# Car_Circuitry.net
KiCad netlist of a schematic drawn in Altium Designer
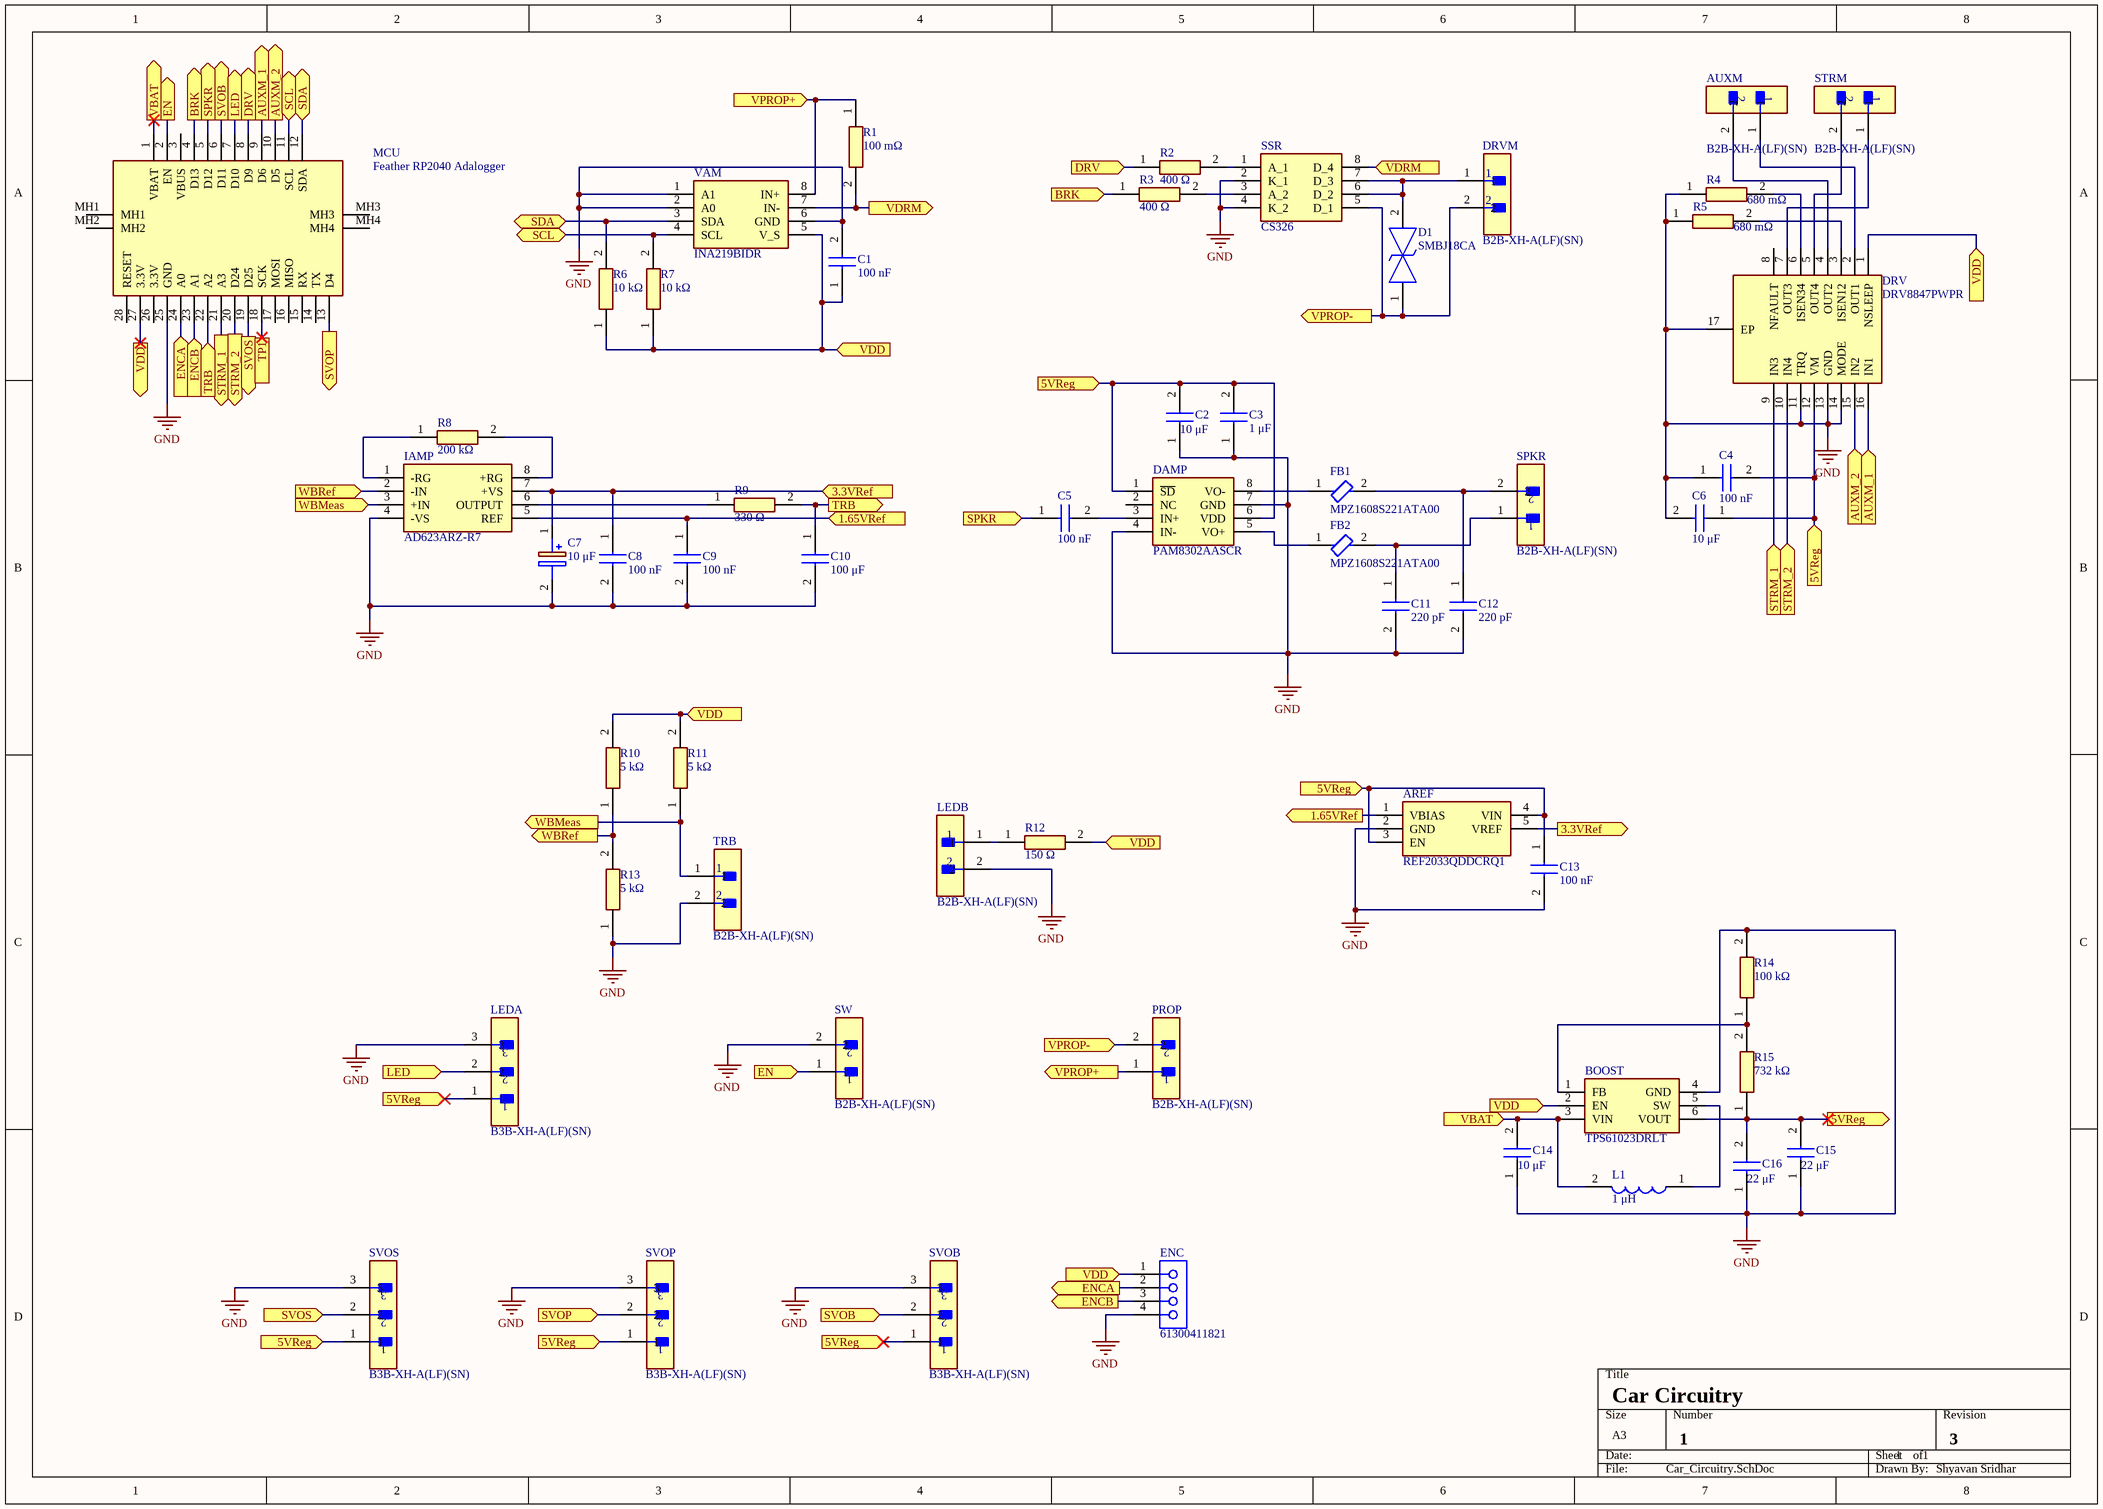
[diagram p0: Car_Circuitry.SchDoc]

(export (version "E")
  (design (tool "Eeschema 10.0.6"))
  (components
    (comp (ref "AREF")
      (value "REF2033QDDCRQ1")
      (footprint "SamacSys:SOT95P280X110-5N")
      (description "Integrated Circuit")
      (fields (field (name "MOUSER PART NUMBER") "595-REF2033QDDCRQ1"))
      (libsource (lib "*") (part "REF2033QDDCRQ1"))
    )
    (comp (ref "AUXM")
      (value "B2B-XH-A(LF)(SN)")
      (footprint "FP-B2B-XH-A_LF_SN-MFG")
      (description "CONN HEADER VERT 2POS 2.5MM")
      (libsource (lib "Altium Content Vault") (part "3bc925449376181038e59eaffc5286c"))
    )
    (comp (ref "BOOST")
      (value "TPS61023DRLT")
      (footprint "SamacSys:SOTFL50P160X60-6N")
      (description "Integrated Circuit")
      (fields (field (name "MOUSER PART NUMBER") "595-TPS61023DRLT"))
      (libsource (lib "*") (part "TPS61023DRLT"))
    )
    (comp (ref "C1")
      (value "100 nF")
      (footprint "SamacSys:CAPC2012X95N")
      (description "Capacitor")
      (fields
        (field (name "MANUFACTURER_PART_NUMBER") "CL21B104KBCNNNC")
        (field (name "MOUSER PART NUMBER") "187-CL21B104KBCNNNC")
      )
      (libsource (lib "SamacSys") (part "CL21B104KBCNNNC"))
    )
    (comp (ref "C2")
      (value "10 μF")
      (footprint "CAPC2012X140N")
      (description "Capacitor")
      (fields
        (field (name "MANUFACTURER_PART_NUMBER") "CL21B106KOQNNNE")
        (field (name "MOUSER PART NUMBER") "187-CL21B106KOQNNNE")
      )
      (libsource (lib "SamacSys") (part "CL21B106KOQNNNE"))
    )
    (comp (ref "C3")
      (value "1 μF")
      (footprint "SamacSys:C0402C104J4RACTU")
      (description "Capacitor")
      (fields
        (field (name "MANUFACTURER_PART_NUMBER") "C0402C105K9PACTU")
        (field (name "MOUSER PART NUMBER") "80-C0402C105K9P")
      )
      (libsource (lib "SamacSys") (part "C0402C105K9PACTU"))
    )
    (comp (ref "C4")
      (value "100 nF")
      (footprint "SamacSys:CAPC2012X95N")
      (description "Capacitor")
      (fields
        (field (name "MANUFACTURER_PART_NUMBER") "CL21B104KBCNNNC")
        (field (name "MOUSER PART NUMBER") "187-CL21B104KBCNNNC")
      )
      (libsource (lib "SamacSys") (part "CL21B104KBCNNNC"))
    )
    (comp (ref "C5")
      (value "100 nF")
      (footprint "SamacSys:CAPC2012X95N")
      (description "Capacitor")
      (fields
        (field (name "MANUFACTURER_PART_NUMBER") "CL21B104KBCNNNC")
        (field (name "MOUSER PART NUMBER") "187-CL21B104KBCNNNC")
      )
      (libsource (lib "SamacSys") (part "CL21B104KBCNNNC"))
    )
    (comp (ref "C6")
      (value "10 μF")
      (footprint "SamacSys:CAPC2012X140N")
      (description "Capacitor")
      (fields
        (field (name "MANUFACTURER_PART_NUMBER") "CL21B106KOQNNNE")
        (field (name "MOUSER PART NUMBER") "187-CL21B106KOQNNNE")
      )
      (libsource (lib "*") (part "CL21B106KOQNNNE"))
    )
    (comp (ref "C7")
      (value "10 μF")
      (footprint "SamacSys:CAPPM3528X210N")
      (description "Capacitor Polarised")
      (fields
        (field (name "MANUFACTURER_PART_NUMBER") "293D106X9016B2TE3")
        (field (name "MOUSER PART NUMBER") "74-293D106X9016B2TE3")
      )
      (libsource (lib "*") (part "293D106X9016B2TE3"))
    )
    (comp (ref "C8")
      (value "100 nF")
      (footprint "SamacSys:CAPC2012X95N")
      (description "Capacitor")
      (fields
        (field (name "MANUFACTURER_PART_NUMBER") "CL21B104KBCNNNC")
        (field (name "MOUSER PART NUMBER") "187-CL21B104KBCNNNC")
      )
      (libsource (lib "SamacSys") (part "CL21B104KBCNNNC"))
    )
    (comp (ref "C9")
      (value "100 nF")
      (footprint "SamacSys:CAPC2012X95N")
      (description "Capacitor")
      (fields
        (field (name "MANUFACTURER_PART_NUMBER") "CL21B104KBCNNNC")
        (field (name "MOUSER PART NUMBER") "187-CL21B104KBCNNNC")
      )
      (libsource (lib "SamacSys") (part "CL21B104KBCNNNC"))
    )
    (comp (ref "C10")
      (value "100 μF")
      (footprint "SamacSys:GRM31x")
      (description "Capacitor")
      (fields
        (field (name "MANUFACTURER_PART_NUMBER") "GRM31CD80J107MEA8K")
        (field (name "MOUSER PART NUMBER") "81-GRM31CD80J107MA8K")
      )
      (libsource (lib "*") (part "GRM31CD80J107MEA8K"))
    )
    (comp (ref "C11")
      (value "220 pF")
      (footprint "SamacSys:GRM033D70J224ME01D")
      (description "Capacitor")
      (fields
        (field (name "MANUFACTURER_PART_NUMBER") "GRM033R71C221KA01D")
        (field (name "MOUSER PART NUMBER") "81-GRM033R71C221KA1D")
      )
      (libsource (lib "*") (part "GRM033R71C221KA01D"))
    )
    (comp (ref "C12")
      (value "220 pF")
      (footprint "SamacSys:GRM033D70J224ME01D")
      (description "Capacitor")
      (fields
        (field (name "MANUFACTURER_PART_NUMBER") "GRM033R71C221KA01D")
        (field (name "MOUSER PART NUMBER") "81-GRM033R71C221KA1D")
      )
      (libsource (lib "*") (part "GRM033R71C221KA01D"))
    )
    (comp (ref "C13")
      (value "100 nF")
      (footprint "SamacSys:CAPC2012X95N")
      (description "Capacitor")
      (fields
        (field (name "MANUFACTURER_PART_NUMBER") "CL21B104KBCNNNC")
        (field (name "MOUSER PART NUMBER") "187-CL21B104KBCNNNC")
      )
      (libsource (lib "SamacSys") (part "CL21B104KBCNNNC"))
    )
    (comp (ref "C14")
      (value "10 μF")
      (footprint "SamacSys:CAPC2012X140N")
      (description "Capacitor")
      (fields
        (field (name "MANUFACTURER_PART_NUMBER") "CL21B106KOQNNNE")
        (field (name "MOUSER PART NUMBER") "187-CL21B106KOQNNNE")
      )
      (libsource (lib "*") (part "CL21B106KOQNNNE"))
    )
    (comp (ref "C15")
      (value "22 μF")
      (footprint "SamacSys:CAPC3216X180N")
      (description "Capacitor")
      (fields
        (field (name "MANUFACTURER_PART_NUMBER") "CL31B226KPHNNNE")
        (field (name "MOUSER PART NUMBER") "187-CL31B226KPHNNNE")
      )
      (libsource (lib "*") (part "CL31B226KPHNNNE"))
    )
    (comp (ref "C16")
      (value "22 μF")
      (footprint "SamacSys:CAPC3216X180N")
      (description "Capacitor")
      (fields
        (field (name "MANUFACTURER_PART_NUMBER") "CL31B226KPHNNNE")
        (field (name "MOUSER PART NUMBER") "187-CL31B226KPHNNNE")
      )
      (libsource (lib "*") (part "CL31B226KPHNNNE"))
    )
    (comp (ref "D1")
      (value "SMBJ18CA")
      (footprint "SamacSys:DIOM5436X261N")
      (description "TVS Diode (Bi-directional)")
      (fields (field (name "MOUSER PART NUMBER") "576-SMBJ18CA"))
      (libsource (lib "*") (part "SMBJ18CA"))
    )
    (comp (ref "DAMP")
      (value "PAM8302AASCR")
      (footprint "SamacSys:SOP65P490X110-8N")
      (description "Integrated Circuit")
      (fields (field (name "MOUSER PART NUMBER") "621-PAM8302AASCR"))
      (libsource (lib "SamacSys") (part "PAM8302AASCR"))
    )
    (comp (ref "DRV")
      (value "DRV8847PWPR")
      (footprint "SamacSys:SOP65P640X120-17N")
      (description "Integrated Circuit")
      (fields (field (name "MOUSER PART NUMBER") "595-DRV8847PWPR"))
      (libsource (lib "SamacSys") (part "DRV8847PWPR"))
    )
    (comp (ref "DRVM")
      (value "B2B-XH-A(LF)(SN)")
      (footprint "FP-B2B-XH-A_LF_SN-MFG")
      (description "CONN HEADER VERT 2POS 2.5MM")
      (libsource (lib "Altium Content Vault") (part "3bc925449376181038e59eaffc5286c"))
    )
    (comp (ref "ENC")
      (value "61300411821")
      (footprint "61300411821")
      (description "THT Vertical Socket Header WR-PHD, Pitch 2.54 mm, Single Row, 4 pins")
      (libsource (lib "Altium Content Vault") (part "Header_Female_1R_04P"))
    )
    (comp (ref "FB1")
      (value "MPZ1608S221ATA00")
      (footprint "FP-MPZ1608-0_8-MFG")
      (description "Power line Ferrite Bead 220Ω @ 100MHz 2.2A DCR 0.05Ω SMD 0603")
      (fields (field (name "TOLERANCE") "25%"))
      (libsource (lib "Altium Content Vault") (part "5f30dd21d616792df468990f7003faa"))
    )
    (comp (ref "FB2")
      (value "MPZ1608S221ATA00")
      (footprint "FP-MPZ1608-0_8-MFG")
      (description "Power line Ferrite Bead 220Ω @ 100MHz 2.2A DCR 0.05Ω SMD 0603")
      (fields (field (name "TOLERANCE") "25%"))
      (libsource (lib "Altium Content Vault") (part "5f30dd21d616792df468990f7003faa"))
    )
    (comp (ref "IAMP")
      (value "AD623ARZ-R7")
      (footprint "SamacSys:SOIC127P600X175-8N")
      (description "Integrated Circuit")
      (fields
        (field (name "MANUFACTURER_PART_NUMBER") "AD623AR-REEL7")
        (field (name "MOUSER PART NUMBER") "584-AD623AR-R7")
      )
      (libsource (lib "*") (part "AD623AR-REEL7"))
    )
    (comp (ref "L1")
      (value "1 μH")
      (footprint "SamacSys:74438357010")
      (description "Inductor")
      (fields
        (field (name "MANUFACTURER_PART_NUMBER") "74438357010")
        (field (name "MOUSER PART NUMBER") "710-74438357010")
      )
      (libsource (lib "*") (part "74438357010"))
    )
    (comp (ref "LEDA")
      (value "B3B-XH-A(LF)(SN)")
      (footprint "FP-B3B-XH-A_LF_SN-MFG")
      (description "CONN HEADER VERT 3POS 2.5MM")
      (libsource (lib "Altium Content Vault") (part "0d3f023dd272f625e17a2be33dea85f"))
    )
    (comp (ref "LEDB")
      (value "B2B-XH-A(LF)(SN)")
      (footprint "FP-B2B-XH-A_LF_SN-MFG")
      (description "CONN HEADER VERT 2POS 2.5MM")
      (libsource (lib "") (part "3bc925449376181038e59eaffc5286c_2"))
    )
    (comp (ref "MCU")
      (value "Feather RP2040 Adalogger")
      (footprint "SamacSys:2796")
      (description "Adafruit Microcontroller")
      (fields (field (name "MANUFACTURER_PART_NUMBER") "4884") (field (name "MOUSER PART NUMBER") "485-5980"))
      (libsource (lib "*") (part "2796"))
    )
    (comp (ref "PROP")
      (value "B2B-XH-A(LF)(SN)")
      (footprint "FP-B2B-XH-A_LF_SN-MFG")
      (description "CONN HEADER VERT 2POS 2.5MM")
      (libsource (lib "") (part "3bc925449376181038e59eaffc5286c_1"))
    )
    (comp (ref "R1")
      (value "100 mΩ")
      (footprint "SamacSys:RESC2013X65N")
      (description "Resistor")
      (fields
        (field (name "MANUFACTURER_PART_NUMBER") "RCWE0805R100FKEA")
        (field (name "MOUSER PART NUMBER") "71-RCWE0805R100FKEA")
      )
      (libsource (lib "*") (part "RCWE0805R100FKEA"))
    )
    (comp (ref "R2")
      (value "400 Ω")
      (footprint "SamacSys:RESC1608X46N")
      (description "Resistor")
      (fields
        (field (name "MANUFACTURER_PART_NUMBER") "PAT0603E4000BST1")
        (field (name "MOUSER PART NUMBER") "71-PAT0603E4000BST1")
      )
      (libsource (lib "*") (part "PAT0603E4000BST1"))
    )
    (comp (ref "R3")
      (value "400 Ω")
      (footprint "SamacSys:RESC1608X46N")
      (description "Resistor")
      (fields
        (field (name "MANUFACTURER_PART_NUMBER") "PAT0603E4000BST1")
        (field (name "MOUSER PART NUMBER") "71-PAT0603E4000BST1")
      )
      (libsource (lib "*") (part "PAT0603E4000BST1"))
    )
    (comp (ref "R4")
      (value "680 mΩ")
      (footprint "SamacSys:ERJ6_B_BW_R_LW_CW_D")
      (description "Resistor")
      (fields (field (name "MANUFACTURER_PART_NUMBER") "ERJ-6DQJR68V"))
      (libsource (lib "SamacSys") (part "ERJ-6DQJR68V"))
    )
    (comp (ref "R5")
      (value "680 mΩ")
      (footprint "SamacSys:ERJ6_B_BW_R_LW_CW_D")
      (description "Resistor")
      (fields (field (name "MANUFACTURER_PART_NUMBER") "ERJ-6DQJR68V"))
      (libsource (lib "SamacSys") (part "ERJ-6DQJR68V"))
    )
    (comp (ref "R6")
      (value "10 kΩ")
      (footprint "SamacSys:RESC1005X40N")
      (description "Resistor")
      (fields
        (field (name "MANUFACTURER_PART_NUMBER") "RC0402JR-0710KL")
        (field (name "MOUSER PART NUMBER") "603-RC0402JR-0710KL")
      )
      (libsource (lib "*") (part "RC0402JR-0710KL"))
    )
    (comp (ref "R7")
      (value "10 kΩ")
      (footprint "SamacSys:RESC1005X40N")
      (description "Resistor")
      (fields
        (field (name "MANUFACTURER_PART_NUMBER") "RC0402JR-0710KL")
        (field (name "MOUSER PART NUMBER") "603-RC0402JR-0710KL")
      )
      (libsource (lib "*") (part "RC0402JR-0710KL"))
    )
    (comp (ref "R8")
      (value "200 kΩ")
      (footprint "SamacSys:ERA6AEB101V")
      (description "Resistor")
      (fields
        (field (name "MANUFACTURER_PART_NUMBER") "ERA-6AEB204V")
        (field (name "MOUSER PART NUMBER") "667-ERA-6AEB204V")
      )
      (libsource (lib "*") (part "ERA-6AEB204V"))
    )
    (comp (ref "R9")
      (value "330 Ω")
      (footprint "SamacSys:RESC1005X40N")
      (description "Resistor")
      (fields
        (field (name "MANUFACTURER_PART_NUMBER") "RC0402FR-07330RL")
        (field (name "MOUSER PART NUMBER") "603-RC0402FR-07330RL")
      )
      (libsource (lib "*") (part "RC0402FR-07330RL"))
    )
    (comp (ref "R10")
      (value "5 kΩ")
      (footprint "SamacSys:RESC0603X26N")
      (description "Resistor")
      (fields
        (field (name "MANUFACTURER_PART_NUMBER") "TNPW02015K00BEED")
        (field (name "MOUSER PART NUMBER") "71-TNPW02015K00BEED")
      )
      (libsource (lib "*") (part "TNPW02015K00BEED"))
    )
    (comp (ref "R11")
      (value "5 kΩ")
      (footprint "SamacSys:RESC0603X26N")
      (description "Resistor")
      (fields
        (field (name "MANUFACTURER_PART_NUMBER") "TNPW02015K00BEED")
        (field (name "MOUSER PART NUMBER") "71-TNPW02015K00BEED")
      )
      (libsource (lib "*") (part "TNPW02015K00BEED"))
    )
    (comp (ref "R12")
      (value "150 Ω")
      (footprint "SamacSys:RESC2012X60N")
      (description "Resistor")
      (fields
        (field (name "MANUFACTURER_PART_NUMBER") "RK73B2ATTD151J")
        (field (name "MOUSER PART NUMBER") "660-RK73B2ATTD151J")
      )
      (libsource (lib "*") (part "RK73B2ATTD151J"))
    )
    (comp (ref "R13")
      (value "5 kΩ")
      (footprint "SamacSys:RESC0603X26N")
      (description "Resistor")
      (fields
        (field (name "MANUFACTURER_PART_NUMBER") "TNPW02015K00BEED")
        (field (name "MOUSER PART NUMBER") "71-TNPW02015K00BEED")
      )
      (libsource (lib "*") (part "TNPW02015K00BEED"))
    )
    (comp (ref "R14")
      (value "100 kΩ")
      (footprint "SamacSys:ERJ8ENF1000V")
      (description "Resistor")
      (fields
        (field (name "MANUFACTURER_PART_NUMBER") "ERJ-8ENF1003V")
        (field (name "MOUSER PART NUMBER") "667-ERJ-8ENF1003V")
      )
      (libsource (lib "*") (part "ERJ-8ENF1003V"))
    )
    (comp (ref "R15")
      (value "732 kΩ")
      (footprint "SamacSys:ERJ8ENF1000V")
      (description "Resistor")
      (fields
        (field (name "MANUFACTURER_PART_NUMBER") "ERJ-8ENF7323V")
        (field (name "MOUSER PART NUMBER") "667-ERJ-8ENF7323V")
      )
      (libsource (lib "*") (part "ERJ-8ENF7323V"))
    )
    (comp (ref "SPKR")
      (value "B2B-XH-A(LF)(SN)")
      (footprint "FP-B2B-XH-A_LF_SN-MFG")
      (description "CONN HEADER VERT 2POS 2.5MM")
      (libsource (lib "") (part "3bc925449376181038e59eaffc5286c_1"))
    )
    (comp (ref "SSR")
      (value "CS326")
      (footprint "SamacSys:SOP254P1030X390-8N")
      (description "Relay or Contactor")
      (fields (field (name "MOUSER PART NUMBER") "816-CS326"))
      (libsource (lib "*") (part "CS326"))
    )
    (comp (ref "STRM")
      (value "B2B-XH-A(LF)(SN)")
      (footprint "FP-B2B-XH-A_LF_SN-MFG")
      (description "CONN HEADER VERT 2POS 2.5MM")
      (libsource (lib "Altium Content Vault") (part "3bc925449376181038e59eaffc5286c"))
    )
    (comp (ref "SVOB")
      (value "B3B-XH-A(LF)(SN)")
      (footprint "FP-B3B-XH-A_LF_SN-MFG")
      (description "CONN HEADER VERT 3POS 2.5MM")
      (libsource (lib "Altium Content Vault") (part "0d3f023dd272f625e17a2be33dea85f"))
    )
    (comp (ref "SVOP")
      (value "B3B-XH-A(LF)(SN)")
      (footprint "FP-B3B-XH-A_LF_SN-MFG")
      (description "CONN HEADER VERT 3POS 2.5MM")
      (libsource (lib "Altium Content Vault") (part "0d3f023dd272f625e17a2be33dea85f"))
    )
    (comp (ref "SVOS")
      (value "B3B-XH-A(LF)(SN)")
      (footprint "FP-B3B-XH-A_LF_SN-MFG")
      (description "CONN HEADER VERT 3POS 2.5MM")
      (libsource (lib "Altium Content Vault") (part "0d3f023dd272f625e17a2be33dea85f"))
    )
    (comp (ref "SW")
      (value "B2B-XH-A(LF)(SN)")
      (footprint "FP-B2B-XH-A_LF_SN-MFG")
      (description "CONN HEADER VERT 2POS 2.5MM")
      (libsource (lib "") (part "3bc925449376181038e59eaffc5286c_1"))
    )
    (comp (ref "TRB")
      (value "B2B-XH-A(LF)(SN)")
      (footprint "FP-B2B-XH-A_LF_SN-MFG")
      (description "CONN HEADER VERT 2POS 2.5MM")
      (libsource (lib "Altium Content Vault") (part "3bc925449376181038e59eaffc5286c"))
    )
    (comp (ref "VAM")
      (value "INA219BIDR")
      (footprint "SamacSys:SOIC127P600X175-8N")
      (description "Integrated Circuit")
      (fields (field (name "MOUSER PART NUMBER") "595-INA219BIDR"))
      (libsource (lib "*") (part "INA219BIDR"))
    )
  )
  (nets
    (net (code "1") (name "/1.65VRef") (class "Default")
      (node (ref "AREF") (pin "1") (pinfunction "VBIAS_1") (pintype "passive"))
      (node (ref "C9") (pin "1") (pinfunction "1_1") (pintype "passive"))
      (node (ref "IAMP") (pin "5") (pinfunction "REF_5") (pintype "passive"))
    )
    (net (code "2") (name "/3.3VRef") (class "Default")
      (node (ref "AREF") (pin "5") (pinfunction "VREF_5") (pintype "passive"))
      (node (ref "C7") (pin "1") (pinfunction "+_1") (pintype "passive"))
      (node (ref "C8") (pin "1") (pinfunction "1_1") (pintype "passive"))
      (node (ref "IAMP") (pin "7") (pinfunction "+VS_7") (pintype "passive"))
    )
    (net (code "3") (name "/5VReg") (class "Default")
      (node (ref "AREF") (pin "3") (pinfunction "EN_3") (pintype "passive"))
      (node (ref "AREF") (pin "4") (pinfunction "VIN_4") (pintype "passive"))
      (node (ref "BOOST") (pin "6") (pinfunction "VOUT_6") (pintype "passive"))
      (node (ref "C13") (pin "1") (pinfunction "1_1") (pintype "passive"))
      (node (ref "C15") (pin "2") (pinfunction "2_2") (pintype "passive"))
      (node (ref "C16") (pin "2") (pinfunction "2_2") (pintype "passive"))
      (node (ref "C2") (pin "2") (pinfunction "2_2") (pintype "passive"))
      (node (ref "C3") (pin "2") (pinfunction "2_2") (pintype "passive"))
      (node (ref "C4") (pin "2") (pinfunction "2_2") (pintype "passive"))
      (node (ref "C6") (pin "1") (pinfunction "1_1") (pintype "passive"))
      (node (ref "DAMP") (pin "1") (pinfunction "~{SD}_1") (pintype "passive"))
      (node (ref "DAMP") (pin "6") (pinfunction "VDD_6") (pintype "passive"))
      (node (ref "DRV") (pin "12") (pinfunction "VM_12") (pintype "passive"))
      (node (ref "LEDA") (pin "1") (pinfunction "1_1") (pintype "passive"))
      (node (ref "R15") (pin "1") (pinfunction "1_1") (pintype "passive"))
      (node (ref "SVOB") (pin "1") (pinfunction "1_1") (pintype "passive"))
      (node (ref "SVOP") (pin "1") (pinfunction "1_1") (pintype "passive"))
      (node (ref "SVOS") (pin "1") (pinfunction "1_1") (pintype "passive"))
    )
    (net (code "4") (name "/AUXM_1") (class "Default")
      (node (ref "DRV") (pin "16") (pinfunction "IN1_16") (pintype "passive"))
      (node (ref "MCU") (pin "9") (pinfunction "D6_9") (pintype "passive"))
    )
    (net (code "5") (name "/AUXM_2") (class "Default")
      (node (ref "DRV") (pin "15") (pinfunction "IN2_15") (pintype "passive"))
      (node (ref "MCU") (pin "10") (pinfunction "D5_10") (pintype "passive"))
    )
    (net (code "6") (name "/BRK") (class "Default")
      (node (ref "MCU") (pin "4") (pinfunction "D13_4") (pintype "passive"))
      (node (ref "R3") (pin "1") (pinfunction "1_1") (pintype "passive"))
    )
    (net (code "7") (name "/DRV") (class "Default")
      (node (ref "MCU") (pin "8") (pinfunction "D9_8") (pintype "passive"))
      (node (ref "R2") (pin "1") (pinfunction "1_1") (pintype "passive"))
    )
    (net (code "8") (name "/EN") (class "Default")
      (node (ref "MCU") (pin "2") (pinfunction "EN_2") (pintype "passive"))
      (node (ref "SW") (pin "1") (pinfunction "1_1") (pintype "passive"))
    )
    (net (code "9") (name "/ENCA") (class "Default")
      (node (ref "ENC") (pin "2") (pinfunction "2_2") (pintype "passive"))
      (node (ref "MCU") (pin "24") (pinfunction "A0_24") (pintype "passive"))
    )
    (net (code "10") (name "/ENCB") (class "Default")
      (node (ref "ENC") (pin "3") (pinfunction "3_3") (pintype "passive"))
      (node (ref "MCU") (pin "23") (pinfunction "A1_23") (pintype "passive"))
    )
    (net (code "11") (name "/LED") (class "Default")
      (node (ref "LEDA") (pin "2") (pinfunction "2_2") (pintype "passive"))
      (node (ref "MCU") (pin "7") (pinfunction "D10_7") (pintype "passive"))
    )
    (net (code "12") (name "/SCL") (class "Default")
      (node (ref "MCU") (pin "11") (pinfunction "SCL_11") (pintype "passive"))
      (node (ref "R7") (pin "2") (pinfunction "2_2") (pintype "passive"))
      (node (ref "VAM") (pin "4") (pinfunction "SCL_4") (pintype "passive"))
    )
    (net (code "13") (name "/SDA") (class "Default")
      (node (ref "MCU") (pin "12") (pinfunction "SDA_12") (pintype "passive"))
      (node (ref "R6") (pin "2") (pinfunction "2_2") (pintype "passive"))
      (node (ref "VAM") (pin "3") (pinfunction "SDA_3") (pintype "passive"))
    )
    (net (code "14") (name "/SPKR") (class "Default")
      (node (ref "C5") (pin "1") (pinfunction "1_1") (pintype "passive"))
      (node (ref "MCU") (pin "5") (pinfunction "D12_5") (pintype "passive"))
    )
    (net (code "15") (name "/STRM_1") (class "Default")
      (node (ref "DRV") (pin "9") (pinfunction "IN3_9") (pintype "passive"))
      (node (ref "MCU") (pin "21") (pinfunction "A3_21") (pintype "passive"))
    )
    (net (code "16") (name "/STRM_2") (class "Default")
      (node (ref "DRV") (pin "10") (pinfunction "IN4_10") (pintype "passive"))
      (node (ref "MCU") (pin "20") (pinfunction "D24_20") (pintype "passive"))
    )
    (net (code "17") (name "/SVOB") (class "Default")
      (node (ref "MCU") (pin "6") (pinfunction "D11_6") (pintype "passive"))
      (node (ref "SVOB") (pin "2") (pinfunction "2_2") (pintype "passive"))
    )
    (net (code "18") (name "/SVOP") (class "Default")
      (node (ref "MCU") (pin "13") (pinfunction "D4_13") (pintype "passive"))
      (node (ref "SVOP") (pin "2") (pinfunction "2_2") (pintype "passive"))
    )
    (net (code "19") (name "/SVOS") (class "Default")
      (node (ref "MCU") (pin "19") (pinfunction "D25_19") (pintype "passive"))
      (node (ref "SVOS") (pin "2") (pinfunction "2_2") (pintype "passive"))
    )
    (net (code "20") (name "/TP1") (class "Default")
      (node (ref "MCU") (pin "18") (pinfunction "SCK_18") (pintype "passive+no_connect"))
    )
    (net (code "21") (name "/TRB") (class "Default")
      (node (ref "C10") (pin "1") (pinfunction "1_1") (pintype "passive"))
      (node (ref "MCU") (pin "22") (pinfunction "A2_22") (pintype "passive"))
      (node (ref "R9") (pin "2") (pinfunction "2_2") (pintype "passive"))
    )
    (net (code "22") (name "/VBAT") (class "Default")
      (node (ref "BOOST") (pin "3") (pinfunction "VIN_3") (pintype "passive"))
      (node (ref "C14") (pin "2") (pinfunction "2_2") (pintype "passive"))
      (node (ref "L1") (pin "2") (pinfunction "2_2") (pintype "passive"))
      (node (ref "MCU") (pin "1") (pinfunction "VBAT_1") (pintype "passive"))
    )
    (net (code "23") (name "/VDD") (class "Default")
      (node (ref "BOOST") (pin "2") (pinfunction "EN_2") (pintype "passive"))
      (node (ref "C1") (pin "1") (pinfunction "1_1") (pintype "passive"))
      (node (ref "DRV") (pin "1") (pinfunction "NSLEEP_1") (pintype "passive"))
      (node (ref "ENC") (pin "1") (pinfunction "1_1") (pintype "passive"))
      (node (ref "MCU") (pin "27") (pinfunction "3.3V_27") (pintype "passive"))
      (node (ref "R10") (pin "2") (pinfunction "2_2") (pintype "passive"))
      (node (ref "R11") (pin "2") (pinfunction "2_2") (pintype "passive"))
      (node (ref "R12") (pin "2") (pinfunction "2_2") (pintype "passive"))
      (node (ref "R6") (pin "1") (pinfunction "1_1") (pintype "passive"))
      (node (ref "R7") (pin "1") (pinfunction "1_1") (pintype "passive"))
      (node (ref "VAM") (pin "5") (pinfunction "V_S_5") (pintype "passive"))
    )
    (net (code "24") (name "/VDRM") (class "Default")
      (node (ref "R1") (pin "2") (pinfunction "2_2") (pintype "passive"))
      (node (ref "SSR") (pin "8") (pinfunction "D_4_8") (pintype "passive"))
      (node (ref "VAM") (pin "7") (pinfunction "IN-_7") (pintype "passive"))
    )
    (net (code "25") (name "/VPROP+") (class "Default")
      (node (ref "PROP") (pin "1") (pinfunction "1_1") (pintype "passive"))
      (node (ref "R1") (pin "1") (pinfunction "1_1") (pintype "passive"))
      (node (ref "VAM") (pin "8") (pinfunction "IN+_8") (pintype "passive"))
    )
    (net (code "26") (name "/VPROP-") (class "Default")
      (node (ref "D1") (pin "1") (pinfunction "1_1") (pintype "passive"))
      (node (ref "DRVM") (pin "2") (pinfunction "2_2") (pintype "passive"))
      (node (ref "PROP") (pin "2") (pinfunction "2_2") (pintype "passive"))
      (node (ref "SSR") (pin "5") (pinfunction "D_1_5") (pintype "passive"))
    )
    (net (code "27") (name "/WBMeas") (class "Default")
      (node (ref "IAMP") (pin "3") (pinfunction "+IN_3") (pintype "passive"))
      (node (ref "R11") (pin "1") (pinfunction "1_1") (pintype "passive"))
      (node (ref "TRB") (pin "1") (pinfunction "1_1") (pintype "passive"))
    )
    (net (code "28") (name "/WBRef") (class "Default")
      (node (ref "IAMP") (pin "2") (pinfunction "-IN_2") (pintype "passive"))
      (node (ref "R10") (pin "1") (pinfunction "1_1") (pintype "passive"))
      (node (ref "R13") (pin "2") (pinfunction "2_2") (pintype "passive"))
    )
    (net (code "29") (name "GND") (class "Default")
      (node (ref "AREF") (pin "2") (pinfunction "GND_2") (pintype "passive"))
      (node (ref "BOOST") (pin "4") (pinfunction "GND_4") (pintype "passive"))
      (node (ref "C1") (pin "2") (pinfunction "2_2") (pintype "passive"))
      (node (ref "C10") (pin "2") (pinfunction "2_2") (pintype "passive"))
      (node (ref "C11") (pin "2") (pinfunction "2_2") (pintype "passive"))
      (node (ref "C12") (pin "2") (pinfunction "2_2") (pintype "passive"))
      (node (ref "C13") (pin "2") (pinfunction "2_2") (pintype "passive"))
      (node (ref "C14") (pin "1") (pinfunction "1_1") (pintype "passive"))
      (node (ref "C15") (pin "1") (pinfunction "1_1") (pintype "passive"))
      (node (ref "C16") (pin "1") (pinfunction "1_1") (pintype "passive"))
      (node (ref "C2") (pin "1") (pinfunction "1_1") (pintype "passive"))
      (node (ref "C3") (pin "1") (pinfunction "1_1") (pintype "passive"))
      (node (ref "C4") (pin "1") (pinfunction "1_1") (pintype "passive"))
      (node (ref "C6") (pin "2") (pinfunction "2_2") (pintype "passive"))
      (node (ref "C7") (pin "2") (pinfunction "-_2") (pintype "passive"))
      (node (ref "C8") (pin "2") (pinfunction "2_2") (pintype "passive"))
      (node (ref "C9") (pin "2") (pinfunction "2_2") (pintype "passive"))
      (node (ref "DAMP") (pin "4") (pinfunction "IN-_4") (pintype "passive"))
      (node (ref "DAMP") (pin "7") (pinfunction "GND_7") (pintype "passive"))
      (node (ref "DRV") (pin "11") (pinfunction "TRQ_11") (pintype "passive"))
      (node (ref "DRV") (pin "13") (pinfunction "GND_13") (pintype "passive"))
      (node (ref "DRV") (pin "14") (pinfunction "MODE_14") (pintype "passive"))
      (node (ref "DRV") (pin "17") (pinfunction "EP_17") (pintype "passive"))
      (node (ref "ENC") (pin "4") (pinfunction "4_4") (pintype "passive"))
      (node (ref "IAMP") (pin "4") (pinfunction "-VS_4") (pintype "passive"))
      (node (ref "LEDA") (pin "3") (pinfunction "3_3") (pintype "passive"))
      (node (ref "LEDB") (pin "2") (pinfunction "2_2") (pintype "passive"))
      (node (ref "MCU") (pin "25") (pinfunction "GND_25") (pintype "passive"))
      (node (ref "R13") (pin "1") (pinfunction "1_1") (pintype "passive"))
      (node (ref "R14") (pin "2") (pinfunction "2_2") (pintype "passive"))
      (node (ref "R4") (pin "1") (pinfunction "1_1") (pintype "passive"))
      (node (ref "R5") (pin "1") (pinfunction "1_1") (pintype "passive"))
      (node (ref "SSR") (pin "2") (pinfunction "K_1_2") (pintype "passive"))
      (node (ref "SSR") (pin "4") (pinfunction "K_2_4") (pintype "passive"))
      (node (ref "SVOB") (pin "3") (pinfunction "3_3") (pintype "passive"))
      (node (ref "SVOP") (pin "3") (pinfunction "3_3") (pintype "passive"))
      (node (ref "SVOS") (pin "3") (pinfunction "3_3") (pintype "passive"))
      (node (ref "SW") (pin "2") (pinfunction "2_2") (pintype "passive"))
      (node (ref "TRB") (pin "2") (pinfunction "2_2") (pintype "passive"))
      (node (ref "VAM") (pin "1") (pinfunction "A1_1") (pintype "passive"))
      (node (ref "VAM") (pin "2") (pinfunction "A0_2") (pintype "passive"))
      (node (ref "VAM") (pin "6") (pinfunction "GND_6") (pintype "passive"))
    )
    (net (code "30") (name "Net-(BOOST-FB)") (class "Default")
      (node (ref "BOOST") (pin "1") (pinfunction "FB_1") (pintype "passive"))
      (node (ref "R14") (pin "1") (pinfunction "1_1") (pintype "passive"))
      (node (ref "R15") (pin "2") (pinfunction "2_2") (pintype "passive"))
    )
    (net (code "31") (name "Net-(BOOST-SW)") (class "Default")
      (node (ref "BOOST") (pin "5") (pinfunction "SW_5") (pintype "passive"))
      (node (ref "L1") (pin "1") (pinfunction "1_1") (pintype "passive"))
    )
    (net (code "32") (name "Net-(C11-Pad1)") (class "Default")
      (node (ref "C11") (pin "1") (pinfunction "1_1") (pintype "passive"))
      (node (ref "FB2") (pin "2") (pinfunction "2_2") (pintype "passive"))
      (node (ref "SPKR") (pin "1") (pinfunction "1_1") (pintype "passive"))
    )
    (net (code "33") (name "Net-(C12-Pad1)") (class "Default")
      (node (ref "C12") (pin "1") (pinfunction "1_1") (pintype "passive"))
      (node (ref "FB1") (pin "2") (pinfunction "2_2") (pintype "passive"))
      (node (ref "SPKR") (pin "2") (pinfunction "2_2") (pintype "passive"))
    )
    (net (code "34") (name "Net-(DAMP-IN+)") (class "Default")
      (node (ref "C5") (pin "2") (pinfunction "2_2") (pintype "passive"))
      (node (ref "DAMP") (pin "3") (pinfunction "IN+_3") (pintype "passive"))
    )
    (net (code "35") (name "Net-(DAMP-VO+)") (class "Default")
      (node (ref "DAMP") (pin "5") (pinfunction "VO+_5") (pintype "passive"))
      (node (ref "FB2") (pin "1") (pinfunction "1_1") (pintype "passive"))
    )
    (net (code "36") (name "Net-(DAMP-VO-)") (class "Default")
      (node (ref "DAMP") (pin "8") (pinfunction "VO-_8") (pintype "passive"))
      (node (ref "FB1") (pin "1") (pinfunction "1_1") (pintype "passive"))
    )
    (net (code "37") (name "Net-(DRV-ISEN12)") (class "Default")
      (node (ref "DRV") (pin "3") (pinfunction "ISEN12_3") (pintype "passive"))
      (node (ref "R5") (pin "2") (pinfunction "2_2") (pintype "passive"))
    )
    (net (code "38") (name "Net-(DRV-ISEN34)") (class "Default")
      (node (ref "DRV") (pin "6") (pinfunction "ISEN34_6") (pintype "passive"))
      (node (ref "R4") (pin "2") (pinfunction "2_2") (pintype "passive"))
    )
    (net (code "39") (name "Net-(DRV-OUT1)") (class "Default")
      (node (ref "AUXM") (pin "1") (pinfunction "1_1") (pintype "passive"))
      (node (ref "DRV") (pin "2") (pinfunction "OUT1_2") (pintype "passive"))
    )
    (net (code "40") (name "Net-(DRV-OUT2)") (class "Default")
      (node (ref "AUXM") (pin "2") (pinfunction "2_2") (pintype "passive"))
      (node (ref "DRV") (pin "4") (pinfunction "OUT2_4") (pintype "passive"))
    )
    (net (code "41") (name "Net-(DRV-OUT3)") (class "Default")
      (node (ref "DRV") (pin "7") (pinfunction "OUT3_7") (pintype "passive"))
      (node (ref "STRM") (pin "1") (pinfunction "1_1") (pintype "passive"))
    )
    (net (code "42") (name "Net-(DRV-OUT4)") (class "Default")
      (node (ref "DRV") (pin "5") (pinfunction "OUT4_5") (pintype "passive"))
      (node (ref "STRM") (pin "2") (pinfunction "2_2") (pintype "passive"))
    )
    (net (code "43") (name "Net-(IAMP-+RG)") (class "Default")
      (node (ref "IAMP") (pin "8") (pinfunction "+RG_8") (pintype "passive"))
      (node (ref "R8") (pin "2") (pinfunction "2_2") (pintype "passive"))
    )
    (net (code "44") (name "Net-(IAMP--RG)") (class "Default")
      (node (ref "IAMP") (pin "1") (pinfunction "-RG_1") (pintype "passive"))
      (node (ref "R8") (pin "1") (pinfunction "1_1") (pintype "passive"))
    )
    (net (code "45") (name "Net-(IAMP-OUTPUT)") (class "Default")
      (node (ref "IAMP") (pin "6") (pinfunction "OUTPUT_6") (pintype "passive"))
      (node (ref "R9") (pin "1") (pinfunction "1_1") (pintype "passive"))
    )
    (net (code "46") (name "Net-(LEDB-Pad1)") (class "Default")
      (node (ref "LEDB") (pin "1") (pinfunction "1_1") (pintype "passive"))
      (node (ref "R12") (pin "1") (pinfunction "1_1") (pintype "passive"))
    )
    (net (code "47") (name "Net-(SSR-A_1)") (class "Default")
      (node (ref "R2") (pin "2") (pinfunction "2_2") (pintype "passive"))
      (node (ref "SSR") (pin "1") (pinfunction "A_1_1") (pintype "passive"))
    )
    (net (code "48") (name "Net-(SSR-A_2)") (class "Default")
      (node (ref "R3") (pin "2") (pinfunction "2_2") (pintype "passive"))
      (node (ref "SSR") (pin "3") (pinfunction "A_2_3") (pintype "passive"))
    )
    (net (code "49") (name "Net-(SSR-D_2)") (class "Default")
      (node (ref "D1") (pin "2") (pinfunction "2_2") (pintype "passive"))
      (node (ref "DRVM") (pin "1") (pinfunction "1_1") (pintype "passive"))
      (node (ref "SSR") (pin "6") (pinfunction "D_2_6") (pintype "passive"))
      (node (ref "SSR") (pin "7") (pinfunction "D_3_7") (pintype "passive"))
    )
    (net (code "50") (name "unconnected-(DAMP-NC-Pad2)") (class "Default")
      (node (ref "DAMP") (pin "2") (pinfunction "NC_2") (pintype "passive"))
    )
    (net (code "51") (name "unconnected-(DRV-NFAULT-Pad8)") (class "Default")
      (node (ref "DRV") (pin "8") (pinfunction "NFAULT_8") (pintype "passive"))
    )
    (net (code "52") (name "unconnected-(MCU-3.3V-Pad26)") (class "Default")
      (node (ref "MCU") (pin "26") (pinfunction "3.3V_26") (pintype "passive"))
    )
    (net (code "53") (name "unconnected-(MCU-MISO-Pad16)") (class "Default")
      (node (ref "MCU") (pin "16") (pinfunction "MISO_16") (pintype "passive"))
    )
    (net (code "54") (name "unconnected-(MCU-MOSI-Pad17)") (class "Default")
      (node (ref "MCU") (pin "17") (pinfunction "MOSI_17") (pintype "passive"))
    )
    (net (code "55") (name "unconnected-(MCU-PadMH1)") (class "Default")
      (node (ref "MCU") (pin "MH1") (pinfunction "MH1_MH1") (pintype "passive"))
    )
    (net (code "56") (name "unconnected-(MCU-PadMH2)") (class "Default")
      (node (ref "MCU") (pin "MH2") (pinfunction "MH2_MH2") (pintype "passive"))
    )
    (net (code "57") (name "unconnected-(MCU-PadMH3)") (class "Default")
      (node (ref "MCU") (pin "MH3") (pinfunction "MH3_MH3") (pintype "passive"))
    )
    (net (code "58") (name "unconnected-(MCU-PadMH4)") (class "Default")
      (node (ref "MCU") (pin "MH4") (pinfunction "MH4_MH4") (pintype "passive"))
    )
    (net (code "59") (name "unconnected-(MCU-RESET-Pad28)") (class "Default")
      (node (ref "MCU") (pin "28") (pinfunction "RESET_28") (pintype "passive"))
    )
    (net (code "60") (name "unconnected-(MCU-RX-Pad15)") (class "Default")
      (node (ref "MCU") (pin "15") (pinfunction "RX_15") (pintype "passive"))
    )
    (net (code "61") (name "unconnected-(MCU-TX-Pad14)") (class "Default")
      (node (ref "MCU") (pin "14") (pinfunction "TX_14") (pintype "passive"))
    )
    (net (code "62") (name "unconnected-(MCU-VBUS-Pad3)") (class "Default")
      (node (ref "MCU") (pin "3") (pinfunction "VBUS_3") (pintype "passive"))
    )
  )
)
